# 2014-11-17.net
KiCad netlist of a schematic drawn in Altium Designer
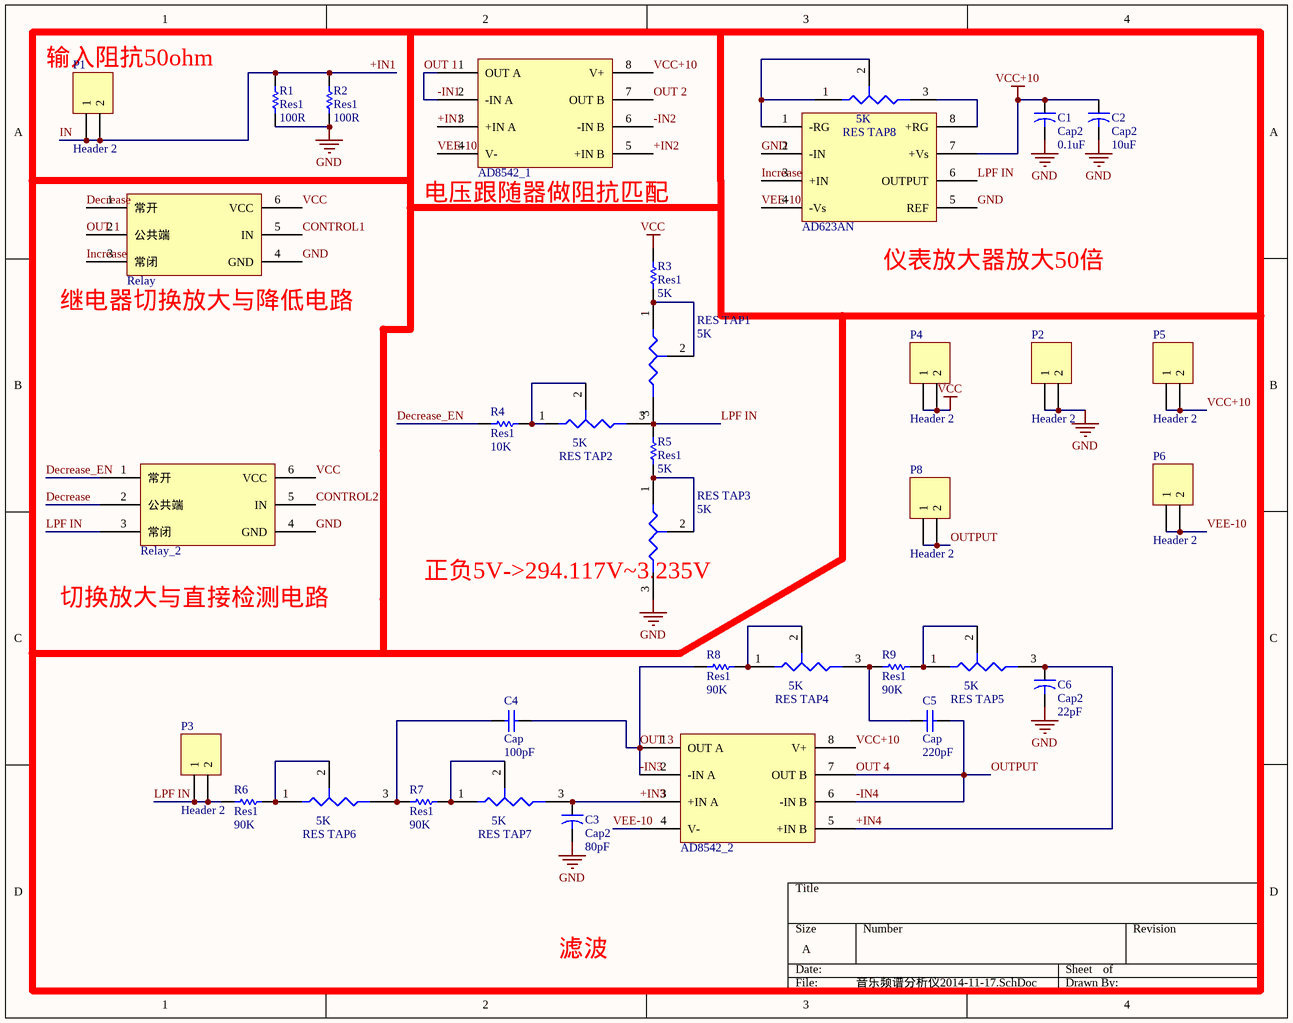
[diagram p0: 音乐频谱分析仪2014-11-17.SchDoc]

(export (version "E")
  (design (tool "Eeschema 10.0.6"))
  (components
    (comp (ref "AD623AN")
      (value "AD623AN")
      (footprint "AD623AN")
      (libsource (lib "my Integrated lib ") (part "AD623AN"))
    )
    (comp (ref "AD8542_1")
      (value "AD8542")
      (footprint "AD8542")
      (libsource (lib "my Integrated lib ") (part "AD8542"))
    )
    (comp (ref "AD8542_2")
      (value "AD8542")
      (footprint "AD8542")
      (libsource (lib "my Integrated lib ") (part "AD8542"))
    )
    (comp (ref "C1")
      (value "Cap2")
      (footprint "BAT-2")
      (description "Capacitor")
      (fields (field (name "ALTIUM_VALUE") "0.1uF") (field (name "PUBLISHER") "Altium Limited"))
      (libsource (lib "Miscellaneous Devices") (part "Cap2"))
    )
    (comp (ref "C2")
      (value "Cap2")
      (footprint "BAT-2")
      (description "Capacitor")
      (fields (field (name "ALTIUM_VALUE") "10uF") (field (name "PUBLISHER") "Altium Limited"))
      (libsource (lib "Miscellaneous Devices") (part "Cap2"))
    )
    (comp (ref "C3")
      (value "Cap2")
      (footprint "BAT-2")
      (description "Capacitor")
      (fields (field (name "ALTIUM_VALUE") "80pF") (field (name "PUBLISHER") "Altium Limited"))
      (libsource (lib "Miscellaneous Devices") (part "Cap2"))
    )
    (comp (ref "C4")
      (value "Cap")
      (footprint "BAT-2")
      (description "Capacitor")
      (fields (field (name "ALTIUM_VALUE") "100pF") (field (name "PUBLISHER") "Altium Limited"))
      (libsource (lib "Miscellaneous Devices") (part "Cap"))
    )
    (comp (ref "C5")
      (value "Cap")
      (footprint "BAT-2")
      (description "Capacitor")
      (fields (field (name "ALTIUM_VALUE") "220pF") (field (name "PUBLISHER") "Altium Limited"))
      (libsource (lib "Miscellaneous Devices") (part "Cap"))
    )
    (comp (ref "C6")
      (value "Cap2")
      (footprint "BAT-2")
      (description "Capacitor")
      (fields (field (name "ALTIUM_VALUE") "22pF") (field (name "PUBLISHER") "Altium Limited"))
      (libsource (lib "Miscellaneous Devices") (part "Cap2"))
    )
    (comp (ref "P1")
      (value "Header 2")
      (footprint "HDR1X2")
      (description "Header, 2-Pin")
      (fields (field (name "PUBLISHER") "Altium Limited"))
      (libsource (lib "Miscellaneous Connectors") (part "Header 2"))
    )
    (comp (ref "P2")
      (value "Header 2")
      (footprint "HDR1X2")
      (description "Header, 2-Pin")
      (fields (field (name "PUBLISHER") "Altium Limited"))
      (libsource (lib "Miscellaneous Connectors") (part "Header 2"))
    )
    (comp (ref "P3")
      (value "Header 2")
      (footprint "HDR1X2")
      (description "Header, 2-Pin")
      (fields (field (name "PUBLISHER") "Altium Limited"))
      (libsource (lib "Miscellaneous Connectors") (part "Header 2"))
    )
    (comp (ref "P4")
      (value "Header 2")
      (footprint "HDR1X2")
      (description "Header, 2-Pin")
      (fields (field (name "PUBLISHER") "Altium Limited"))
      (libsource (lib "Miscellaneous Connectors") (part "Header 2"))
    )
    (comp (ref "P5")
      (value "Header 2")
      (footprint "HDR1X2")
      (description "Header, 2-Pin")
      (fields (field (name "PUBLISHER") "Altium Limited"))
      (libsource (lib "Miscellaneous Connectors") (part "Header 2"))
    )
    (comp (ref "P6")
      (value "Header 2")
      (footprint "HDR1X2")
      (description "Header, 2-Pin")
      (fields (field (name "PUBLISHER") "Altium Limited"))
      (libsource (lib "Miscellaneous Connectors") (part "Header 2"))
    )
    (comp (ref "P8")
      (value "Header 2")
      (footprint "HDR1X2")
      (description "Header, 2-Pin")
      (fields (field (name "PUBLISHER") "Altium Limited"))
      (libsource (lib "Miscellaneous Connectors") (part "Header 2"))
    )
    (comp (ref "R1")
      (value "Res1")
      (footprint "AXIAL-0.3")
      (description "Resistor")
      (fields (field (name "ALTIUM_VALUE") "100R") (field (name "PUBLISHER") "Altium Limited"))
      (libsource (lib "Miscellaneous Devices") (part "Res1"))
    )
    (comp (ref "R2")
      (value "Res1")
      (footprint "AXIAL-0.3")
      (description "Resistor")
      (fields (field (name "ALTIUM_VALUE") "100R") (field (name "PUBLISHER") "Altium Limited"))
      (libsource (lib "Miscellaneous Devices") (part "Res1"))
    )
    (comp (ref "R3")
      (value "Res1")
      (footprint "AXIAL-0.3")
      (description "Resistor")
      (fields (field (name "ALTIUM_VALUE") "5K") (field (name "PUBLISHER") "Altium Limited"))
      (libsource (lib "Miscellaneous Devices") (part "Res1"))
    )
    (comp (ref "R4")
      (value "Res1")
      (footprint "AXIAL-0.3")
      (description "Resistor")
      (fields (field (name "ALTIUM_VALUE") "10K") (field (name "PUBLISHER") "Altium Limited"))
      (libsource (lib "Miscellaneous Devices") (part "Res1"))
    )
    (comp (ref "R5")
      (value "Res1")
      (footprint "AXIAL-0.3")
      (description "Resistor")
      (fields (field (name "ALTIUM_VALUE") "5K") (field (name "PUBLISHER") "Altium Limited"))
      (libsource (lib "Miscellaneous Devices") (part "Res1"))
    )
    (comp (ref "R6")
      (value "Res1")
      (footprint "AXIAL-0.3")
      (description "Resistor")
      (fields (field (name "ALTIUM_VALUE") "90K") (field (name "PUBLISHER") "Altium Limited"))
      (libsource (lib "Miscellaneous Devices") (part "Res1"))
    )
    (comp (ref "R7")
      (value "Res1")
      (footprint "AXIAL-0.3")
      (description "Resistor")
      (fields (field (name "ALTIUM_VALUE") "90K") (field (name "PUBLISHER") "Altium Limited"))
      (libsource (lib "Miscellaneous Devices") (part "Res1"))
    )
    (comp (ref "R8")
      (value "Res1")
      (footprint "AXIAL-0.3")
      (description "Resistor")
      (fields (field (name "ALTIUM_VALUE") "90K") (field (name "PUBLISHER") "Altium Limited"))
      (libsource (lib "Miscellaneous Devices") (part "Res1"))
    )
    (comp (ref "R9")
      (value "Res1")
      (footprint "AXIAL-0.3")
      (description "Resistor")
      (fields (field (name "ALTIUM_VALUE") "90K") (field (name "PUBLISHER") "Altium Limited"))
      (libsource (lib "Miscellaneous Devices") (part "Res1"))
    )
    (comp (ref "Relay")
      (value "Relay")
      (footprint "Relay")
      (libsource (lib "my Integrated lib ") (part "Relay"))
    )
    (comp (ref "Relay_2")
      (value "Relay")
      (footprint "Relay")
      (libsource (lib "my Integrated lib ") (part "Relay"))
    )
    (comp (ref "RES TAP1")
      (value "5K")
      (footprint "RES TAP2")
      (libsource (lib "my Integrated lib ") (part "RES TAP2"))
    )
    (comp (ref "RES TAP2")
      (value "5K")
      (footprint "RES TAP2")
      (libsource (lib "my Integrated lib ") (part "RES TAP2"))
    )
    (comp (ref "RES TAP3")
      (value "5K")
      (footprint "RES TAP2")
      (libsource (lib "my Integrated lib ") (part "RES TAP2"))
    )
    (comp (ref "RES TAP4")
      (value "5K")
      (footprint "RES TAP2")
      (libsource (lib "my Integrated lib ") (part "RES TAP2"))
    )
    (comp (ref "RES TAP5")
      (value "5K")
      (footprint "RES TAP2")
      (libsource (lib "my Integrated lib ") (part "RES TAP2"))
    )
    (comp (ref "RES TAP6")
      (value "5K")
      (footprint "RES TAP2")
      (libsource (lib "my Integrated lib ") (part "RES TAP2"))
    )
    (comp (ref "RES TAP7")
      (value "5K")
      (footprint "RES TAP2")
      (libsource (lib "my Integrated lib ") (part "RES TAP2"))
    )
    (comp (ref "RES TAP8")
      (value "5K")
      (footprint "RES TAP2")
      (libsource (lib "my Integrated lib ") (part "RES TAP2"))
    )
  )
  (nets
    (net (code "1") (name "/+IN1") (class "Default")
      (node (ref "AD8542_1") (pin "3") (pinfunction "+IN_A_3") (pintype "passive"))
      (node (ref "P1") (pin "1") (pinfunction "1_1") (pintype "passive"))
      (node (ref "P1") (pin "2") (pinfunction "2_2") (pintype "passive"))
      (node (ref "R1") (pin "2") (pinfunction "2_2") (pintype "passive"))
      (node (ref "R2") (pin "2") (pinfunction "2_2") (pintype "passive"))
    )
    (net (code "2") (name "/+IN2") (class "Default")
      (node (ref "AD8542_1") (pin "5") (pinfunction "+IN_B_5") (pintype "passive"))
    )
    (net (code "3") (name "/+IN3") (class "Default")
      (node (ref "AD8542_2") (pin "3") (pinfunction "+IN_A_3") (pintype "passive"))
      (node (ref "C3") (pin "1") (pinfunction "1_1") (pintype "passive"))
      (node (ref "RES TAP7") (pin "3") (pinfunction "B_3") (pintype "passive"))
    )
    (net (code "4") (name "/+IN4") (class "Default")
      (node (ref "AD8542_2") (pin "5") (pinfunction "+IN_B_5") (pintype "passive"))
      (node (ref "C6") (pin "1") (pinfunction "1_1") (pintype "passive"))
      (node (ref "RES TAP5") (pin "3") (pinfunction "B_3") (pintype "passive"))
    )
    (net (code "5") (name "/-IN1") (class "Default")
      (node (ref "AD8542_1") (pin "1") (pinfunction "OUT_A_1") (pintype "passive"))
      (node (ref "AD8542_1") (pin "2") (pinfunction "-IN_A_2") (pintype "passive"))
      (node (ref "Relay") (pin "2") (pinfunction "公共端_2") (pintype "passive"))
    )
    (net (code "6") (name "/-IN2") (class "Default")
      (node (ref "AD8542_1") (pin "6") (pinfunction "-IN_B_6") (pintype "passive"))
    )
    (net (code "7") (name "/-IN3") (class "Default")
      (node (ref "AD8542_2") (pin "1") (pinfunction "OUT_A_1") (pintype "passive"))
      (node (ref "AD8542_2") (pin "2") (pinfunction "-IN_A_2") (pintype "passive"))
      (node (ref "C4") (pin "2") (pinfunction "2_2") (pintype "passive"))
      (node (ref "R8") (pin "2") (pinfunction "2_2") (pintype "passive"))
    )
    (net (code "8") (name "/-IN4") (class "Default")
      (node (ref "AD8542_2") (pin "6") (pinfunction "-IN_B_6") (pintype "passive"))
      (node (ref "AD8542_2") (pin "7") (pinfunction "OUT_B_7") (pintype "passive"))
      (node (ref "C5") (pin "2") (pinfunction "2_2") (pintype "passive"))
      (node (ref "P8") (pin "1") (pinfunction "1_1") (pintype "passive"))
      (node (ref "P8") (pin "2") (pinfunction "2_2") (pintype "passive"))
    )
    (net (code "9") (name "/CONTROL1") (class "Default")
      (node (ref "Relay") (pin "5") (pinfunction "IN_5") (pintype "passive"))
    )
    (net (code "10") (name "/CONTROL2") (class "Default")
      (node (ref "Relay_2") (pin "5") (pinfunction "IN_5") (pintype "passive"))
    )
    (net (code "11") (name "/Decrease") (class "Default")
      (node (ref "Relay") (pin "1") (pinfunction "常开_1") (pintype "passive"))
      (node (ref "Relay_2") (pin "2") (pinfunction "公共端_2") (pintype "passive"))
    )
    (net (code "12") (name "/Decrease_EN") (class "Default")
      (node (ref "R4") (pin "2") (pinfunction "2_2") (pintype "passive"))
      (node (ref "Relay_2") (pin "1") (pinfunction "常开_1") (pintype "passive"))
    )
    (net (code "13") (name "/Increase") (class "Default")
      (node (ref "AD623AN") (pin "3") (pinfunction "+IN_3") (pintype "passive"))
      (node (ref "Relay") (pin "3") (pinfunction "常闭_3") (pintype "passive"))
    )
    (net (code "14") (name "/LPF IN") (class "Default")
      (node (ref "AD623AN") (pin "6") (pinfunction "OUTPUT_6") (pintype "passive"))
      (node (ref "P3") (pin "1") (pinfunction "1_1") (pintype "passive"))
      (node (ref "P3") (pin "2") (pinfunction "2_2") (pintype "passive"))
      (node (ref "R5") (pin "2") (pinfunction "2_2") (pintype "passive"))
      (node (ref "R6") (pin "2") (pinfunction "2_2") (pintype "passive"))
      (node (ref "RES TAP1") (pin "3") (pinfunction "B_3") (pintype "passive"))
      (node (ref "RES TAP2") (pin "3") (pinfunction "B_3") (pintype "passive"))
      (node (ref "Relay_2") (pin "3") (pinfunction "常闭_3") (pintype "passive"))
    )
    (net (code "15") (name "/OUT 2") (class "Default")
      (node (ref "AD8542_1") (pin "7") (pinfunction "OUT_B_7") (pintype "passive"))
    )
    (net (code "16") (name "/VEE-10") (class "Default")
      (node (ref "AD623AN") (pin "4") (pinfunction "-Vs_4") (pintype "passive"))
      (node (ref "AD8542_1") (pin "4") (pinfunction "V-_4") (pintype "passive"))
      (node (ref "AD8542_2") (pin "4") (pinfunction "V-_4") (pintype "passive"))
      (node (ref "P6") (pin "1") (pinfunction "1_1") (pintype "passive"))
      (node (ref "P6") (pin "2") (pinfunction "2_2") (pintype "passive"))
    )
    (net (code "17") (name "GND") (class "Default")
      (node (ref "AD623AN") (pin "2") (pinfunction "-IN_2") (pintype "passive"))
      (node (ref "AD623AN") (pin "5") (pinfunction "REF_5") (pintype "passive"))
      (node (ref "C1") (pin "2") (pinfunction "2_2") (pintype "passive"))
      (node (ref "C2") (pin "2") (pinfunction "2_2") (pintype "passive"))
      (node (ref "C3") (pin "2") (pinfunction "2_2") (pintype "passive"))
      (node (ref "C6") (pin "2") (pinfunction "2_2") (pintype "passive"))
      (node (ref "P2") (pin "1") (pinfunction "1_1") (pintype "passive"))
      (node (ref "P2") (pin "2") (pinfunction "2_2") (pintype "passive"))
      (node (ref "R1") (pin "1") (pinfunction "1_1") (pintype "passive"))
      (node (ref "R2") (pin "1") (pinfunction "1_1") (pintype "passive"))
      (node (ref "RES TAP3") (pin "3") (pinfunction "B_3") (pintype "passive"))
      (node (ref "Relay") (pin "4") (pinfunction "GND_4") (pintype "passive"))
      (node (ref "Relay_2") (pin "4") (pinfunction "GND_4") (pintype "passive"))
    )
    (net (code "18") (name "Net-(AD623AN-+RG)") (class "Default")
      (node (ref "AD623AN") (pin "8") (pinfunction "+RG_8") (pintype "passive"))
      (node (ref "RES TAP8") (pin "3") (pinfunction "B_3") (pintype "passive"))
    )
    (net (code "19") (name "Net-(AD623AN--RG)") (class "Default")
      (node (ref "AD623AN") (pin "1") (pinfunction "-RG_1") (pintype "passive"))
      (node (ref "RES TAP8") (pin "1") (pinfunction "A_1") (pintype "passive"))
      (node (ref "RES TAP8") (pin "2") (pinfunction "TAP_2") (pintype "passive"))
    )
    (net (code "20") (name "Net-(RES TAP1-A)") (class "Default")
      (node (ref "R3") (pin "1") (pinfunction "1_1") (pintype "passive"))
      (node (ref "RES TAP1") (pin "1") (pinfunction "A_1") (pintype "passive"))
      (node (ref "RES TAP1") (pin "2") (pinfunction "TAP_2") (pintype "passive"))
    )
    (net (code "21") (name "Net-(RES TAP2-A)") (class "Default")
      (node (ref "R4") (pin "1") (pinfunction "1_1") (pintype "passive"))
      (node (ref "RES TAP2") (pin "1") (pinfunction "A_1") (pintype "passive"))
      (node (ref "RES TAP2") (pin "2") (pinfunction "TAP_2") (pintype "passive"))
    )
    (net (code "22") (name "Net-(RES TAP3-A)") (class "Default")
      (node (ref "R5") (pin "1") (pinfunction "1_1") (pintype "passive"))
      (node (ref "RES TAP3") (pin "1") (pinfunction "A_1") (pintype "passive"))
      (node (ref "RES TAP3") (pin "2") (pinfunction "TAP_2") (pintype "passive"))
    )
    (net (code "23") (name "Net-(RES TAP4-A)") (class "Default")
      (node (ref "R8") (pin "1") (pinfunction "1_1") (pintype "passive"))
      (node (ref "RES TAP4") (pin "1") (pinfunction "A_1") (pintype "passive"))
      (node (ref "RES TAP4") (pin "2") (pinfunction "TAP_2") (pintype "passive"))
    )
    (net (code "24") (name "Net-(RES TAP4-B)") (class "Default")
      (node (ref "C5") (pin "1") (pinfunction "1_1") (pintype "passive"))
      (node (ref "R9") (pin "2") (pinfunction "2_2") (pintype "passive"))
      (node (ref "RES TAP4") (pin "3") (pinfunction "B_3") (pintype "passive"))
    )
    (net (code "25") (name "Net-(RES TAP5-A)") (class "Default")
      (node (ref "R9") (pin "1") (pinfunction "1_1") (pintype "passive"))
      (node (ref "RES TAP5") (pin "1") (pinfunction "A_1") (pintype "passive"))
      (node (ref "RES TAP5") (pin "2") (pinfunction "TAP_2") (pintype "passive"))
    )
    (net (code "26") (name "Net-(RES TAP6-A)") (class "Default")
      (node (ref "R6") (pin "1") (pinfunction "1_1") (pintype "passive"))
      (node (ref "RES TAP6") (pin "1") (pinfunction "A_1") (pintype "passive"))
      (node (ref "RES TAP6") (pin "2") (pinfunction "TAP_2") (pintype "passive"))
    )
    (net (code "27") (name "Net-(RES TAP6-B)") (class "Default")
      (node (ref "C4") (pin "1") (pinfunction "1_1") (pintype "passive"))
      (node (ref "R7") (pin "2") (pinfunction "2_2") (pintype "passive"))
      (node (ref "RES TAP6") (pin "3") (pinfunction "B_3") (pintype "passive"))
    )
    (net (code "28") (name "Net-(RES TAP7-A)") (class "Default")
      (node (ref "R7") (pin "1") (pinfunction "1_1") (pintype "passive"))
      (node (ref "RES TAP7") (pin "1") (pinfunction "A_1") (pintype "passive"))
      (node (ref "RES TAP7") (pin "2") (pinfunction "TAP_2") (pintype "passive"))
    )
    (net (code "29") (name "VCC") (class "Default")
      (node (ref "P4") (pin "1") (pinfunction "1_1") (pintype "passive"))
      (node (ref "P4") (pin "2") (pinfunction "2_2") (pintype "passive"))
      (node (ref "R3") (pin "2") (pinfunction "2_2") (pintype "passive"))
      (node (ref "Relay") (pin "6") (pinfunction "VCC_6") (pintype "passive"))
      (node (ref "Relay_2") (pin "6") (pinfunction "VCC_6") (pintype "passive"))
    )
    (net (code "30") (name "VCC+10") (class "Default")
      (node (ref "AD623AN") (pin "7") (pinfunction "+Vs_7") (pintype "passive"))
      (node (ref "AD8542_1") (pin "8") (pinfunction "V+_8") (pintype "passive"))
      (node (ref "AD8542_2") (pin "8") (pinfunction "V+_8") (pintype "passive"))
      (node (ref "C1") (pin "1") (pinfunction "1_1") (pintype "passive"))
      (node (ref "C2") (pin "1") (pinfunction "1_1") (pintype "passive"))
      (node (ref "P5") (pin "1") (pinfunction "1_1") (pintype "passive"))
      (node (ref "P5") (pin "2") (pinfunction "2_2") (pintype "passive"))
    )
  )
)
